# PetBallLauncher.net
KiCad netlist of a schematic drawn in Altium Designer
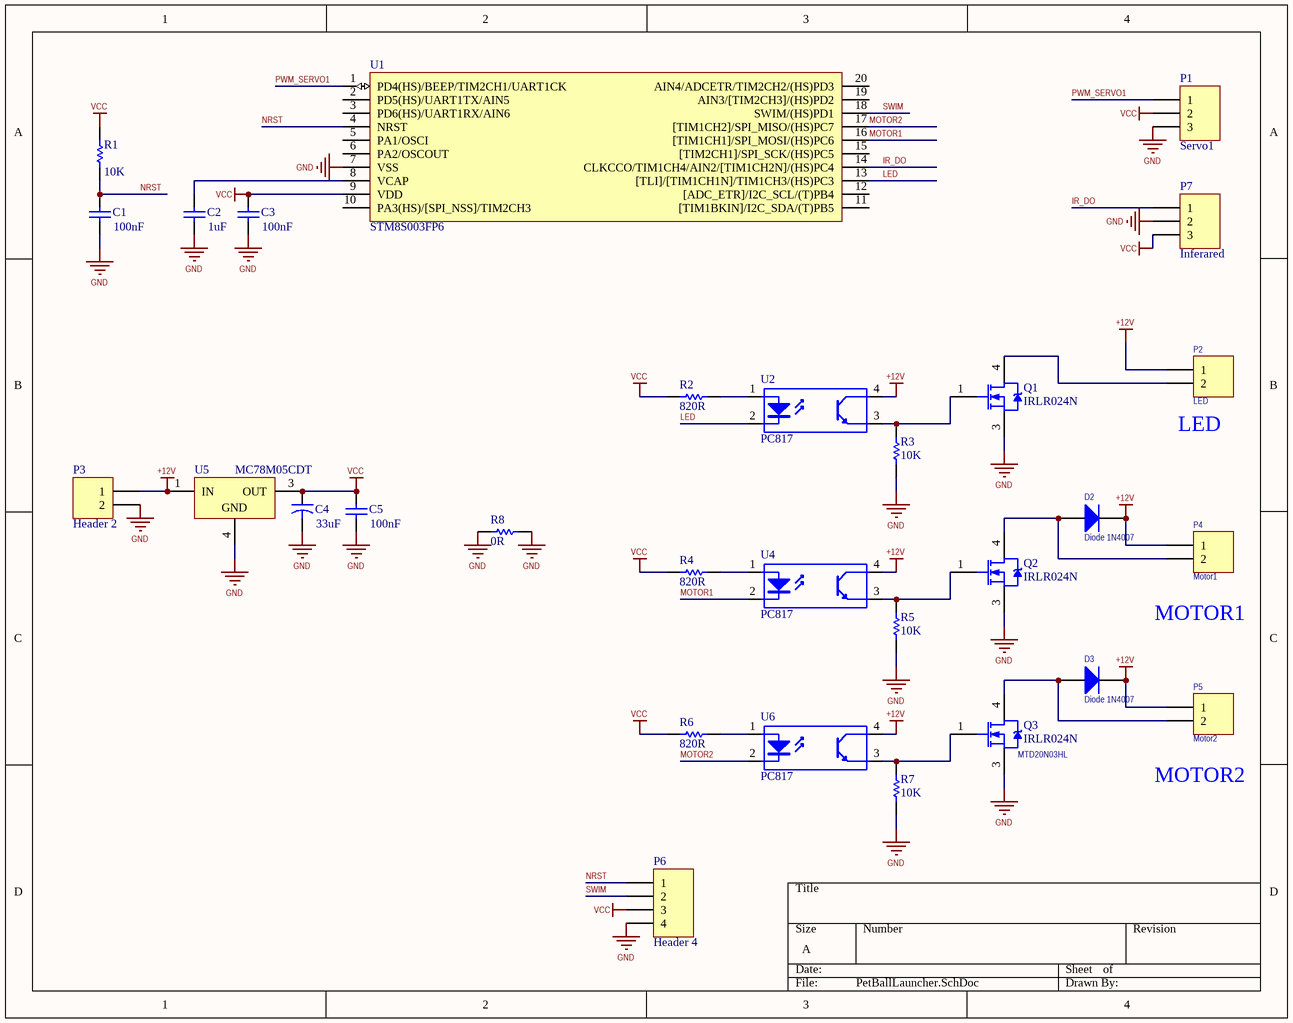
[diagram p0: PetBallLauncher.SchDoc]

(export (version "E")
  (design (tool "Eeschema 10.0.6"))
  (components
    (comp (ref "C1")
      (value "100nF")
      (footprint "CAP_MLCC_RAD_0.1")
      (description "Capacitor")
      (fields (field (name "Comment") "Cap") (field (name "PUBLISHER") "Altium Limited"))
      (libsource (lib "Miscellaneous Devices") (part "Cap"))
    )
    (comp (ref "C2")
      (value "1uF")
      (footprint "CAP_MLCC_RAD_0.1")
      (description "Capacitor")
      (fields (field (name "Comment") "Cap") (field (name "PUBLISHER") "Altium Limited"))
      (libsource (lib "Miscellaneous Devices") (part "Cap"))
    )
    (comp (ref "C3")
      (value "100nF")
      (footprint "CAP_MLCC_RAD_0.1")
      (description "Capacitor")
      (fields (field (name "Comment") "Cap") (field (name "PUBLISHER") "Altium Limited"))
      (libsource (lib "Miscellaneous Devices") (part "Cap"))
    )
    (comp (ref "C4")
      (value "33uF")
      (footprint "Cap electrolitic radial 6x7-2.5")
      (description "Capacitor")
      (fields (field (name "Comment") "Cap2") (field (name "PUBLISHER") "Altium Limited"))
      (libsource (lib "Miscellaneous Devices") (part "Cap2"))
    )
    (comp (ref "C5")
      (value "100nF")
      (footprint "CAP_MLCC_RAD_0.1")
      (description "Capacitor")
      (fields (field (name "Comment") "Cap") (field (name "PUBLISHER") "Altium Limited"))
      (libsource (lib "Miscellaneous Devices") (part "Cap"))
    )
    (comp (ref "D2")
      (value "Diode 1N4007")
      (footprint "DO-241AC")
      (description "1 Amp General Purpose Rectifier")
      (fields (field (name "PUBLISHER") "Altium Limited"))
      (libsource (lib "Miscellaneous Devices") (part "Diode 1N4007"))
    )
    (comp (ref "D3")
      (value "Diode 1N4007")
      (footprint "DO-241AC")
      (description "1 Amp General Purpose Rectifier")
      (fields (field (name "PUBLISHER") "Altium Limited"))
      (libsource (lib "Miscellaneous Devices") (part "Diode 1N4007"))
    )
    (comp (ref "P1")
      (value "Servo1")
      (footprint "HDR_1x3")
      (description "Header, 3-Pin")
      (fields (field (name "PUBLISHER") "Altium Limited"))
      (libsource (lib "Miscellaneous Connectors") (part "Header 3"))
    )
    (comp (ref "P2")
      (value "LED")
      (footprint "KF301 2PIN")
      (description "Header, 2-Pin")
      (fields (field (name "PUBLISHER") "Altium Limited"))
      (libsource (lib "Miscellaneous Connectors") (part "Header 2"))
    )
    (comp (ref "P3")
      (value "Header 2")
      (footprint "KF301 2PIN")
      (description "Header, 2-Pin")
      (fields (field (name "PUBLISHER") "Altium Limited"))
      (libsource (lib "") (part "Header 2_1"))
    )
    (comp (ref "P4")
      (value "Motor1")
      (footprint "KF301 2PIN")
      (description "Header, 2-Pin")
      (fields (field (name "PUBLISHER") "Altium Limited"))
      (libsource (lib "Miscellaneous Connectors") (part "Header 2"))
    )
    (comp (ref "P5")
      (value "Motor2")
      (footprint "KF301 2PIN")
      (description "Header, 2-Pin")
      (fields (field (name "PUBLISHER") "Altium Limited"))
      (libsource (lib "Miscellaneous Connectors") (part "Header 2"))
    )
    (comp (ref "P6")
      (value "Header 4")
      (footprint "HDR1X4")
      (description "Header, 4-Pin")
      (fields (field (name "PUBLISHER") "Altium Limited"))
      (libsource (lib "Miscellaneous Connectors") (part "Header 4"))
    )
    (comp (ref "P7")
      (value "Inferared")
      (footprint "HDR_1x3")
      (description "Header, 3-Pin")
      (fields (field (name "PUBLISHER") "Altium Limited"))
      (libsource (lib "Miscellaneous Connectors") (part "Header 3"))
    )
    (comp (ref "Q1")
      (value "IRLR024N")
      (footprint "TO252-3M")
      (description "HEXFET Power MOSFET")
      (fields (field (name "PUBLISHER") "Altium Limited"))
      (libsource (lib "IR Discrete MOSFET - Power") (part "IRLR024N"))
    )
    (comp (ref "Q2")
      (value "IRLR024N")
      (footprint "TO252-3M")
      (description "HEXFET Power MOSFET")
      (fields (field (name "PUBLISHER") "Altium Limited"))
      (libsource (lib "IR Discrete MOSFET - Power") (part "IRLR024N"))
    )
    (comp (ref "Q3")
      (value "IRLR024N")
      (footprint "TO252-3M")
      (description "HEXFET Power MOSFET")
      (fields (field (name "PUBLISHER") "Altium Limited"))
      (libsource (lib "IR Discrete MOSFET - Power") (part "IRLR024N"))
    )
    (comp (ref "R1")
      (value "10K")
      (footprint "Axial 0_25 W, 0_4 IN LEAD PITCH")
      (description "Resistor")
      (fields (field (name "Comment") "Res1") (field (name "PUBLISHER") "Altium Limited"))
      (libsource (lib "Miscellaneous Devices") (part "Res1"))
    )
    (comp (ref "R2")
      (value "820R")
      (footprint "RES0805")
      (description "Resistor")
      (fields (field (name "PUBLISHER") "Altium Limited"))
      (libsource (lib "Miscellaneous Devices") (part "Res1"))
    )
    (comp (ref "R3")
      (value "10K")
      (footprint "RES0805")
      (description "Resistor")
      (fields (field (name "PUBLISHER") "Altium Limited"))
      (libsource (lib "Miscellaneous Devices") (part "Res1"))
    )
    (comp (ref "R4")
      (value "820R")
      (footprint "RES0805")
      (description "Resistor")
      (fields (field (name "PUBLISHER") "Altium Limited"))
      (libsource (lib "Miscellaneous Devices") (part "Res1"))
    )
    (comp (ref "R5")
      (value "10K")
      (footprint "RES0805")
      (description "Resistor")
      (fields (field (name "PUBLISHER") "Altium Limited"))
      (libsource (lib "Miscellaneous Devices") (part "Res1"))
    )
    (comp (ref "R6")
      (value "820R")
      (footprint "RES0805")
      (description "Resistor")
      (fields (field (name "PUBLISHER") "Altium Limited"))
      (libsource (lib "Miscellaneous Devices") (part "Res1"))
    )
    (comp (ref "R7")
      (value "10K")
      (footprint "RES0805")
      (description "Resistor")
      (fields (field (name "PUBLISHER") "Altium Limited"))
      (libsource (lib "Miscellaneous Devices") (part "Res1"))
    )
    (comp (ref "R8")
      (value "0R")
      (footprint "axial-0.3")
      (description "Resistor")
      (fields (field (name "PUBLISHER") "Altium Limited"))
      (libsource (lib "Miscellaneous Devices") (part "Res1"))
    )
    (comp (ref "U1")
      (value "STM8S003FP6")
      (footprint "TSSOP20")
      (description "8 bit microcontroller")
      (libsource (lib "Mofidi3D") (part "STM8S003F3Px"))
    )
    (comp (ref "U2")
      (value "PC817")
      (footprint "DIP_4")
      (description "4-Pin Phototransistor Optocoupler")
      (fields (field (name "PUBLISHER") "Altium Limited"))
      (libsource (lib "Miscellaneous Devices") (part "Optoisolator1"))
    )
    (comp (ref "U4")
      (value "PC817")
      (footprint "DIP_4")
      (description "4-Pin Phototransistor Optocoupler")
      (fields (field (name "PUBLISHER") "Altium Limited"))
      (libsource (lib "Miscellaneous Devices") (part "Optoisolator1"))
    )
    (comp (ref "U5")
      (value "MC78M05CDT")
      (footprint "TO252-3M")
      (description "3-Terminal Medium-Current Positive Fixed Voltage Regulator")
      (fields (field (name "PUBLISHER") "Altium Limited"))
      (libsource (lib "Motorola Power Mgt Voltage Regulator") (part "MC78M05CDT"))
    )
    (comp (ref "U6")
      (value "PC817")
      (footprint "DIP_4")
      (description "4-Pin Phototransistor Optocoupler")
      (fields (field (name "PUBLISHER") "Altium Limited"))
      (libsource (lib "Miscellaneous Devices") (part "Optoisolator1"))
    )
  )
  (nets
    (net (code "1") (name "+12V") (class "Default")
      (node (ref "D2") (pin "2") (pinfunction "K_2") (pintype "passive"))
      (node (ref "D3") (pin "2") (pinfunction "K_2") (pintype "passive"))
      (node (ref "P2") (pin "1") (pinfunction "1_1") (pintype "passive"))
      (node (ref "P3") (pin "1") (pinfunction "1_1") (pintype "passive"))
      (node (ref "P4") (pin "1") (pinfunction "1_1") (pintype "passive"))
      (node (ref "P5") (pin "1") (pinfunction "1_1") (pintype "passive"))
      (node (ref "U2") (pin "4") (pinfunction "C_4") (pintype "passive"))
      (node (ref "U4") (pin "4") (pinfunction "C_4") (pintype "passive"))
      (node (ref "U5") (pin "1") (pinfunction "IN_1") (pintype "power_in"))
      (node (ref "U6") (pin "4") (pinfunction "C_4") (pintype "passive"))
    )
    (net (code "2") (name "/IR_DO") (class "Default")
      (node (ref "P7") (pin "1") (pinfunction "1_1") (pintype "passive"))
      (node (ref "U1") (pin "14") (pinfunction "CLKCCO/TIM1CH4/AIN2/[TIM1CH2N]/(HS)PC4_14") (pintype "passive"))
    )
    (net (code "3") (name "/LED") (class "Default")
      (node (ref "U1") (pin "13") (pinfunction "[TLI]/[TIM1CH1N]/TIM1CH3/(HS)PC3_13") (pintype "passive"))
      (node (ref "U2") (pin "2") (pinfunction "K_2") (pintype "passive"))
    )
    (net (code "4") (name "/MOTOR1") (class "Default")
      (node (ref "U1") (pin "16") (pinfunction "[TIM1CH1]/SPI_MOSI/(HS)PC6_16") (pintype "passive"))
      (node (ref "U4") (pin "2") (pinfunction "K_2") (pintype "passive"))
    )
    (net (code "5") (name "/MOTOR2") (class "Default")
      (node (ref "U1") (pin "17") (pinfunction "[TIM1CH2]/SPI_MISO/(HS)PC7_17") (pintype "passive"))
      (node (ref "U6") (pin "2") (pinfunction "K_2") (pintype "passive"))
    )
    (net (code "6") (name "/NRST") (class "Default")
      (node (ref "C1") (pin "2") (pinfunction "2_2") (pintype "passive"))
      (node (ref "P6") (pin "1") (pinfunction "1_1") (pintype "passive"))
      (node (ref "R1") (pin "1") (pinfunction "1_1") (pintype "passive"))
      (node (ref "U1") (pin "4") (pinfunction "NRST_4") (pintype "passive"))
    )
    (net (code "7") (name "/PWM_SERVO1") (class "Default")
      (node (ref "P1") (pin "1") (pinfunction "1_1") (pintype "passive"))
      (node (ref "U1") (pin "1") (pinfunction "PD4(HS)/BEEP/TIM2CH1/UART1CK_1") (pintype "bidirectional"))
    )
    (net (code "8") (name "/SWIM") (class "Default")
      (node (ref "P6") (pin "2") (pinfunction "2_2") (pintype "passive"))
      (node (ref "U1") (pin "18") (pinfunction "SWIM/(HS)PD1_18") (pintype "passive"))
    )
    (net (code "9") (name "GND") (class "Default")
      (node (ref "C1") (pin "1") (pinfunction "1_1") (pintype "passive"))
      (node (ref "C2") (pin "1") (pinfunction "1_1") (pintype "passive"))
      (node (ref "C3") (pin "1") (pinfunction "1_1") (pintype "passive"))
      (node (ref "C4") (pin "2") (pinfunction "2_2") (pintype "passive"))
      (node (ref "C5") (pin "1") (pinfunction "1_1") (pintype "passive"))
      (node (ref "P1") (pin "3") (pinfunction "3_3") (pintype "passive"))
      (node (ref "P3") (pin "2") (pinfunction "2_2") (pintype "passive"))
      (node (ref "P6") (pin "4") (pinfunction "4_4") (pintype "passive"))
      (node (ref "P7") (pin "2") (pinfunction "2_2") (pintype "passive"))
      (node (ref "Q1") (pin "3") (pinfunction "S_3") (pintype "passive"))
      (node (ref "Q2") (pin "3") (pinfunction "S_3") (pintype "passive"))
      (node (ref "Q3") (pin "3") (pinfunction "S_3") (pintype "passive"))
      (node (ref "R3") (pin "1") (pinfunction "1_1") (pintype "passive"))
      (node (ref "R5") (pin "1") (pinfunction "1_1") (pintype "passive"))
      (node (ref "R7") (pin "1") (pinfunction "1_1") (pintype "passive"))
      (node (ref "R8") (pin "1") (pinfunction "1_1") (pintype "passive"))
      (node (ref "R8") (pin "2") (pinfunction "2_2") (pintype "passive"))
      (node (ref "U1") (pin "7") (pinfunction "VSS_7") (pintype "passive"))
      (node (ref "U5") (pin "4") (pinfunction "GND_4") (pintype "power_in"))
    )
    (net (code "10") (name "Net-(D2-A)") (class "Default")
      (node (ref "D2") (pin "1") (pinfunction "A_1") (pintype "passive"))
      (node (ref "P4") (pin "2") (pinfunction "2_2") (pintype "passive"))
      (node (ref "Q2") (pin "4") (pinfunction "D_4") (pintype "passive"))
    )
    (net (code "11") (name "Net-(D3-A)") (class "Default")
      (node (ref "D3") (pin "1") (pinfunction "A_1") (pintype "passive"))
      (node (ref "P5") (pin "2") (pinfunction "2_2") (pintype "passive"))
      (node (ref "Q3") (pin "4") (pinfunction "D_4") (pintype "passive"))
    )
    (net (code "12") (name "Net-(Q1-D)") (class "Default")
      (node (ref "P2") (pin "2") (pinfunction "2_2") (pintype "passive"))
      (node (ref "Q1") (pin "4") (pinfunction "D_4") (pintype "passive"))
    )
    (net (code "13") (name "Net-(Q1-G)") (class "Default")
      (node (ref "Q1") (pin "1") (pinfunction "G_1") (pintype "passive"))
      (node (ref "R3") (pin "2") (pinfunction "2_2") (pintype "passive"))
      (node (ref "U2") (pin "3") (pinfunction "E_3") (pintype "passive"))
    )
    (net (code "14") (name "Net-(Q2-G)") (class "Default")
      (node (ref "Q2") (pin "1") (pinfunction "G_1") (pintype "passive"))
      (node (ref "R5") (pin "2") (pinfunction "2_2") (pintype "passive"))
      (node (ref "U4") (pin "3") (pinfunction "E_3") (pintype "passive"))
    )
    (net (code "15") (name "Net-(Q3-G)") (class "Default")
      (node (ref "Q3") (pin "1") (pinfunction "G_1") (pintype "passive"))
      (node (ref "R7") (pin "2") (pinfunction "2_2") (pintype "passive"))
      (node (ref "U6") (pin "3") (pinfunction "E_3") (pintype "passive"))
    )
    (net (code "16") (name "Net-(U1-VCAP)") (class "Default")
      (node (ref "C2") (pin "2") (pinfunction "2_2") (pintype "passive"))
      (node (ref "U1") (pin "8") (pinfunction "VCAP_8") (pintype "passive"))
    )
    (net (code "17") (name "Net-(U2-A)") (class "Default")
      (node (ref "R2") (pin "2") (pinfunction "2_2") (pintype "passive"))
      (node (ref "U2") (pin "1") (pinfunction "A_1") (pintype "passive"))
    )
    (net (code "18") (name "Net-(U4-A)") (class "Default")
      (node (ref "R4") (pin "2") (pinfunction "2_2") (pintype "passive"))
      (node (ref "U4") (pin "1") (pinfunction "A_1") (pintype "passive"))
    )
    (net (code "19") (name "Net-(U6-A)") (class "Default")
      (node (ref "R6") (pin "2") (pinfunction "2_2") (pintype "passive"))
      (node (ref "U6") (pin "1") (pinfunction "A_1") (pintype "passive"))
    )
    (net (code "20") (name "VCC") (class "Default")
      (node (ref "C3") (pin "2") (pinfunction "2_2") (pintype "passive"))
      (node (ref "C4") (pin "1") (pinfunction "1_1") (pintype "passive"))
      (node (ref "C5") (pin "2") (pinfunction "2_2") (pintype "passive"))
      (node (ref "P1") (pin "2") (pinfunction "2_2") (pintype "passive"))
      (node (ref "P6") (pin "3") (pinfunction "3_3") (pintype "passive"))
      (node (ref "P7") (pin "3") (pinfunction "3_3") (pintype "passive"))
      (node (ref "R1") (pin "2") (pinfunction "2_2") (pintype "passive"))
      (node (ref "R2") (pin "1") (pinfunction "1_1") (pintype "passive"))
      (node (ref "R4") (pin "1") (pinfunction "1_1") (pintype "passive"))
      (node (ref "R6") (pin "1") (pinfunction "1_1") (pintype "passive"))
      (node (ref "U1") (pin "9") (pinfunction "VDD_9") (pintype "passive"))
      (node (ref "U5") (pin "3") (pinfunction "OUT_3") (pintype "power_in"))
    )
    (net (code "21") (name "unconnected-(U1-AIN3{slash}[TIM2CH3]{slash}(HS)PD2-Pad19)") (class "Default")
      (node (ref "U1") (pin "19") (pinfunction "AIN3/[TIM2CH3]/(HS)PD2_19") (pintype "passive"))
    )
    (net (code "22") (name "unconnected-(U1-AIN4{slash}ADCETR{slash}TIM2CH2{slash}(HS)PD3-Pad20)") (class "Default")
      (node (ref "U1") (pin "20") (pinfunction "AIN4/ADCETR/TIM2CH2/(HS)PD3_20") (pintype "passive"))
    )
    (net (code "23") (name "unconnected-(U1-PA1{slash}OSCI-Pad5)") (class "Default")
      (node (ref "U1") (pin "5") (pinfunction "PA1/OSCI_5") (pintype "passive"))
    )
    (net (code "24") (name "unconnected-(U1-PA2{slash}OSCOUT-Pad6)") (class "Default")
      (node (ref "U1") (pin "6") (pinfunction "PA2/OSCOUT_6") (pintype "passive"))
    )
    (net (code "25") (name "unconnected-(U1-PA3(HS){slash}[SPI_NSS]{slash}TIM2CH3-Pad10)") (class "Default")
      (node (ref "U1") (pin "10") (pinfunction "PA3(HS)/[SPI_NSS]/TIM2CH3_10") (pintype "passive"))
    )
    (net (code "26") (name "unconnected-(U1-PD5(HS){slash}UART1TX{slash}AIN5-Pad2)") (class "Default")
      (node (ref "U1") (pin "2") (pinfunction "PD5(HS)/UART1TX/AIN5_2") (pintype "passive"))
    )
    (net (code "27") (name "unconnected-(U1-PD6(HS){slash}UART1RX{slash}AIN6-Pad3)") (class "Default")
      (node (ref "U1") (pin "3") (pinfunction "PD6(HS)/UART1RX/AIN6_3") (pintype "passive"))
    )
    (net (code "28") (name "unconnected-(U1-[ADC_ETR]{slash}I2C_SCL{slash}(T)PB4-Pad12)") (class "Default")
      (node (ref "U1") (pin "12") (pinfunction "[ADC_ETR]/I2C_SCL/(T)PB4_12") (pintype "passive"))
    )
    (net (code "29") (name "unconnected-(U1-[TIM1BKIN]{slash}I2C_SDA{slash}(T)PB5-Pad11)") (class "Default")
      (node (ref "U1") (pin "11") (pinfunction "[TIM1BKIN]/I2C_SDA/(T)PB5_11") (pintype "passive"))
    )
    (net (code "30") (name "unconnected-(U1-[TIM2CH1]{slash}SPI_SCK{slash}(HS)PC5-Pad15)") (class "Default")
      (node (ref "U1") (pin "15") (pinfunction "[TIM2CH1]/SPI_SCK/(HS)PC5_15") (pintype "passive"))
    )
  )
)
